# explorator_mainboard_v1_99mm.net
KiCad netlist of a schematic drawn in EAGLE
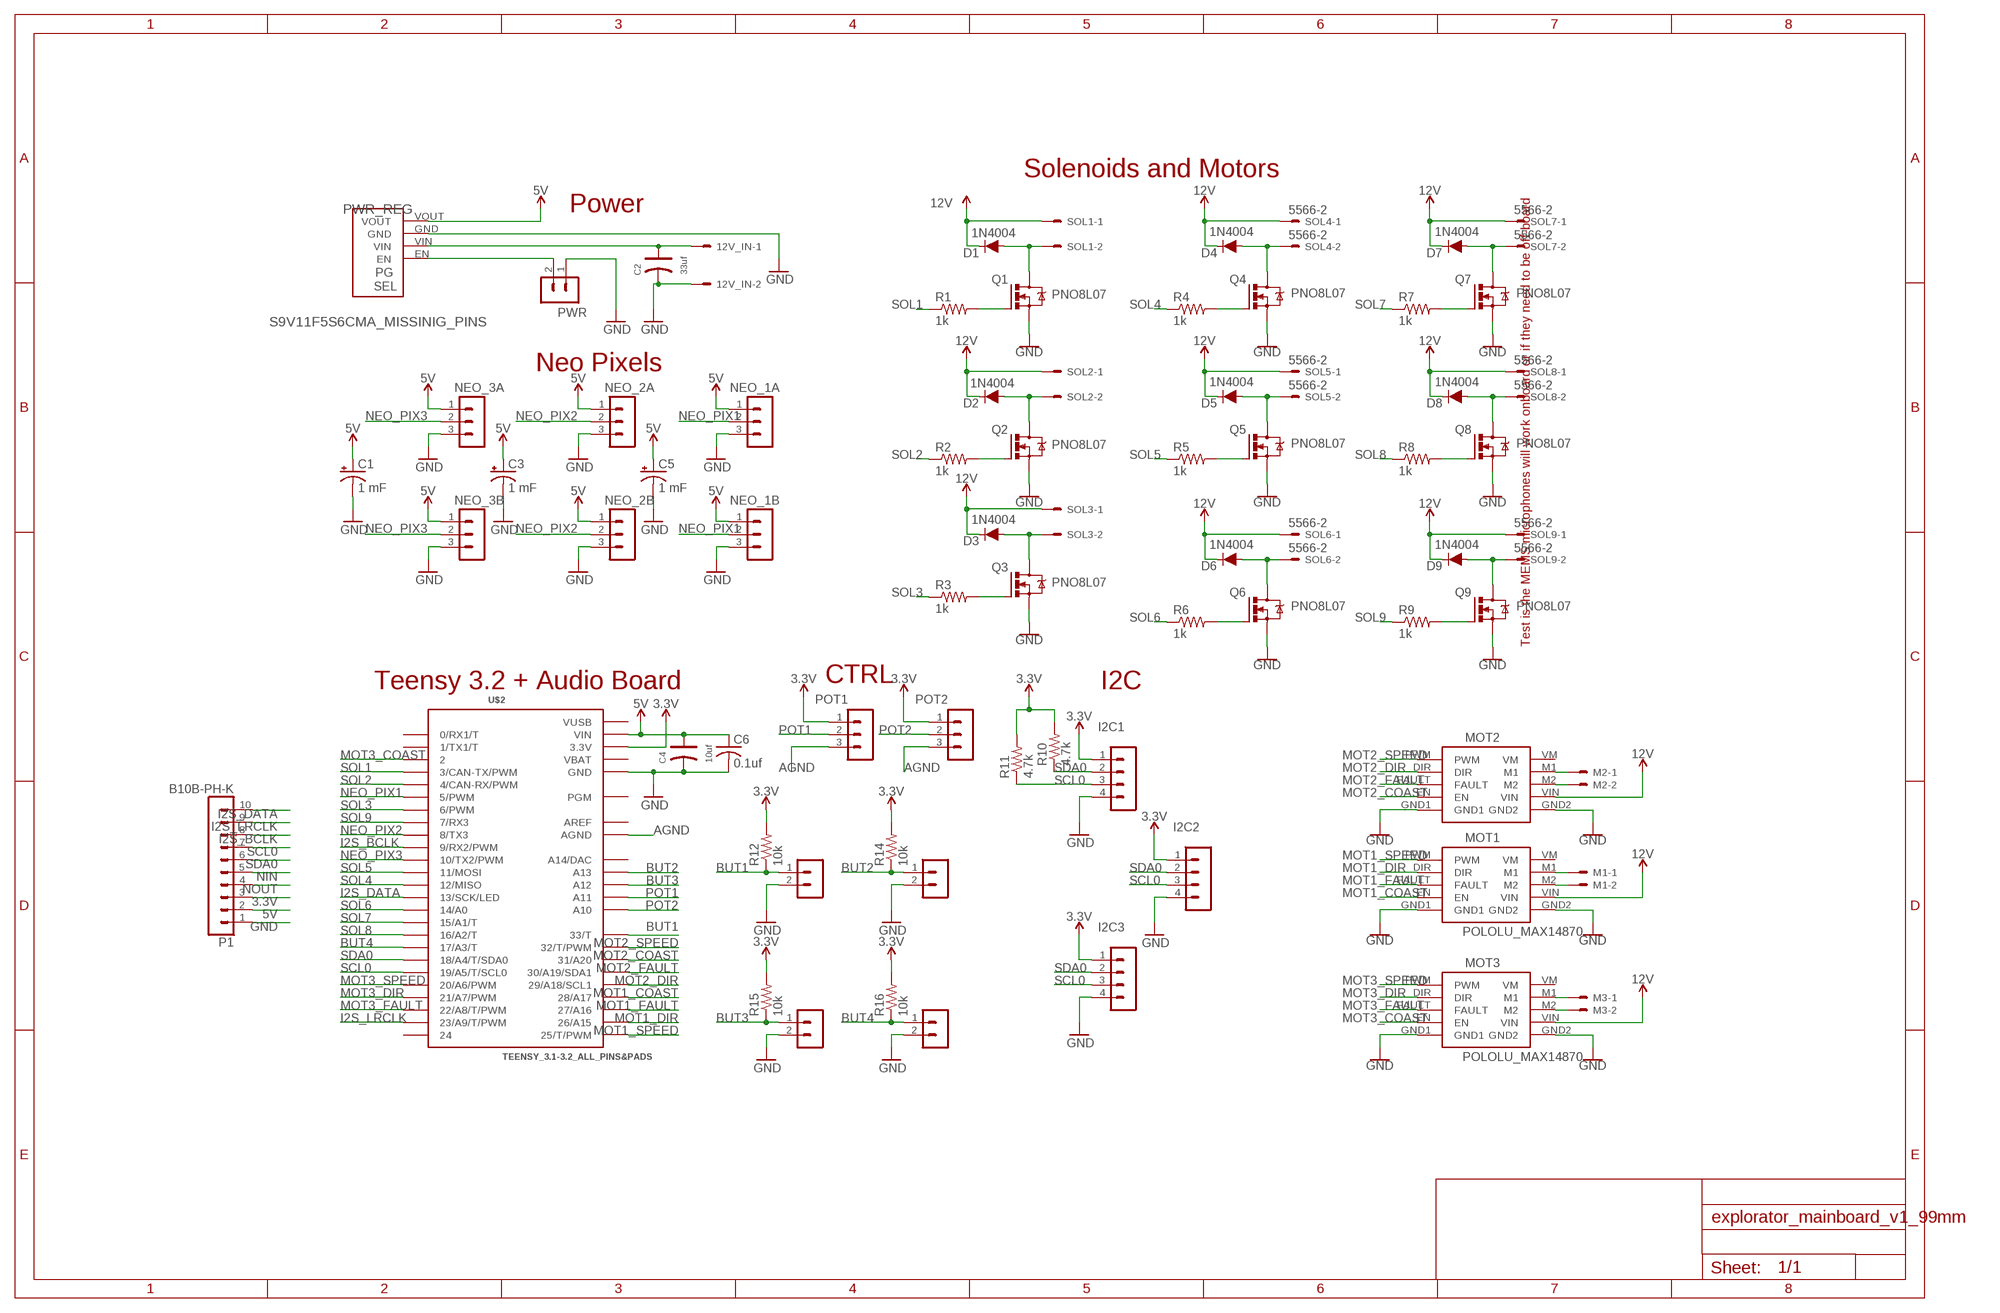
[diagram p0: schematic, sheet 1]

(export (version "E")
  (design (tool "Eeschema 10.0.6"))
  (components
    (comp (ref "12V_IN")
      (value "5566-2")
      (footprint "eagle-import:5566-2")
      (fields (field (name "MF") "MOLEX"))
      (libsource (lib "eagle-import") (part "5566-2"))
    )
    (comp (ref "BUT1")
      (value "B2B-PH-K")
      (footprint "eagle-import:B2B-PH-K")
      (libsource (lib "eagle-import") (part "B2B-PH-K"))
    )
    (comp (ref "BUT2")
      (value "B2B-PH-K")
      (footprint "eagle-import:B2B-PH-K")
      (libsource (lib "eagle-import") (part "B2B-PH-K"))
    )
    (comp (ref "BUT3")
      (value "B2B-PH-K")
      (footprint "eagle-import:B2B-PH-K")
      (libsource (lib "eagle-import") (part "B2B-PH-K"))
    )
    (comp (ref "BUT4")
      (value "B2B-PH-K")
      (footprint "eagle-import:B2B-PH-K")
      (libsource (lib "eagle-import") (part "B2B-PH-K"))
    )
    (comp (ref "C1")
      (value "1 mF")
      (footprint "eagle-import:UD-10X10_NICHICON")
      (libsource (lib "eagle-import") (part "CPOL-USUD-10X10"))
    )
    (comp (ref "C2")
      (value "33uf")
      (footprint "eagle-import:PC-D5.3MM")
      (fields (field (name "MPN") "KS 100uF/16V"))
      (libsource (lib "eagle-import") (part "DIP-ALUMINUM-47UF-16V(D5-H7MM)"))
    )
    (comp (ref "C3")
      (value "1 mF")
      (footprint "eagle-import:UD-10X10_NICHICON")
      (libsource (lib "eagle-import") (part "CPOL-USUD-10X10"))
    )
    (comp (ref "C4")
      (value "10uf")
      (footprint "eagle-import:PC-D5.3MM")
      (fields (field (name "MPN") "KS 100uF/16V"))
      (libsource (lib "eagle-import") (part "DIP-ALUMINUM-47UF-16V(D5-H7MM)"))
    )
    (comp (ref "C5")
      (value "1 mF")
      (footprint "eagle-import:UD-10X10_NICHICON")
      (libsource (lib "eagle-import") (part "CPOL-USUD-10X10"))
    )
    (comp (ref "C6")
      (value "0.1uf")
      (footprint "eagle-import:C2012")
      (libsource (lib "eagle-import") (part "C-USC2012"))
    )
    (comp (ref "D1")
      (value "1N4004")
      (footprint "eagle-import:DIOAD1138W86L465D235B")
      (libsource (lib "eagle-import") (part "1N4004"))
    )
    (comp (ref "D2")
      (value "1N4004")
      (footprint "eagle-import:DIOAD1138W86L465D235B")
      (libsource (lib "eagle-import") (part "1N4004"))
    )
    (comp (ref "D3")
      (value "1N4004")
      (footprint "eagle-import:DIOAD1138W86L465D235B")
      (libsource (lib "eagle-import") (part "1N4004"))
    )
    (comp (ref "D4")
      (value "1N4004")
      (footprint "eagle-import:DIOAD1138W86L465D235B")
      (libsource (lib "eagle-import") (part "1N4004"))
    )
    (comp (ref "D5")
      (value "1N4004")
      (footprint "eagle-import:DIOAD1138W86L465D235B")
      (libsource (lib "eagle-import") (part "1N4004"))
    )
    (comp (ref "D6")
      (value "1N4004")
      (footprint "eagle-import:DIOAD1138W86L465D235B")
      (libsource (lib "eagle-import") (part "1N4004"))
    )
    (comp (ref "D7")
      (value "1N4004")
      (footprint "eagle-import:DIOAD1138W86L465D235B")
      (libsource (lib "eagle-import") (part "1N4004"))
    )
    (comp (ref "D8")
      (value "1N4004")
      (footprint "eagle-import:DIOAD1138W86L465D235B")
      (libsource (lib "eagle-import") (part "1N4004"))
    )
    (comp (ref "D9")
      (value "1N4004")
      (footprint "eagle-import:DIOAD1138W86L465D235B")
      (libsource (lib "eagle-import") (part "1N4004"))
    )
    (comp (ref "I2C1")
      (value "B4B-PH-K")
      (footprint "eagle-import:B4B-PH-K")
      (libsource (lib "eagle-import") (part "B4B-PH-K"))
    )
    (comp (ref "I2C2")
      (value "B4B-PH-K")
      (footprint "eagle-import:B4B-PH-K")
      (libsource (lib "eagle-import") (part "B4B-PH-K"))
    )
    (comp (ref "I2C3")
      (value "B4B-PH-K")
      (footprint "eagle-import:B4B-PH-K")
      (libsource (lib "eagle-import") (part "B4B-PH-K"))
    )
    (comp (ref "M1")
      (value "5566-2")
      (footprint "eagle-import:5566-2")
      (fields (field (name "MF") "MOLEX"))
      (libsource (lib "eagle-import") (part "5566-2"))
    )
    (comp (ref "M2")
      (value "5566-2")
      (footprint "eagle-import:5566-2")
      (fields (field (name "MF") "MOLEX"))
      (libsource (lib "eagle-import") (part "5566-2"))
    )
    (comp (ref "M3")
      (value "5566-2")
      (footprint "eagle-import:5566-2")
      (fields (field (name "MF") "MOLEX"))
      (libsource (lib "eagle-import") (part "5566-2"))
    )
    (comp (ref "MOT1")
      (value "POLOLU_MAX14870")
      (footprint "eagle-import:POLOLU_MAX14870")
      (libsource (lib "eagle-import") (part "POLOLU_MAX14870"))
    )
    (comp (ref "MOT2")
      (value "POLOLU_MAX14870")
      (footprint "eagle-import:POLOLU_MAX14870")
      (libsource (lib "eagle-import") (part "POLOLU_MAX14870"))
    )
    (comp (ref "MOT3")
      (value "POLOLU_MAX14870")
      (footprint "eagle-import:POLOLU_MAX14870")
      (libsource (lib "eagle-import") (part "POLOLU_MAX14870"))
    )
    (comp (ref "NEO_1A")
      (value "B3B-PH-K")
      (footprint "eagle-import:B3B-PH-K")
      (libsource (lib "eagle-import") (part "B3B-PH-K"))
    )
    (comp (ref "NEO_1B")
      (value "B3B-PH-K")
      (footprint "eagle-import:B3B-PH-K")
      (libsource (lib "eagle-import") (part "B3B-PH-K"))
    )
    (comp (ref "NEO_2A")
      (value "B3B-PH-K")
      (footprint "eagle-import:B3B-PH-K")
      (libsource (lib "eagle-import") (part "B3B-PH-K"))
    )
    (comp (ref "NEO_2B")
      (value "B3B-PH-K")
      (footprint "eagle-import:B3B-PH-K")
      (libsource (lib "eagle-import") (part "B3B-PH-K"))
    )
    (comp (ref "NEO_3A")
      (value "B3B-PH-K")
      (footprint "eagle-import:B3B-PH-K")
      (libsource (lib "eagle-import") (part "B3B-PH-K"))
    )
    (comp (ref "NEO_3B")
      (value "B3B-PH-K")
      (footprint "eagle-import:B3B-PH-K")
      (libsource (lib "eagle-import") (part "B3B-PH-K"))
    )
    (comp (ref "P1")
      (value "B10B-PH-K")
      (footprint "eagle-import:B10B-PH-K")
      (libsource (lib "eagle-import") (part "B10B-PH-K"))
    )
    (comp (ref "POT1")
      (value "B3B-PH-K")
      (footprint "eagle-import:B3B-PH-K")
      (libsource (lib "eagle-import") (part "B3B-PH-K"))
    )
    (comp (ref "POT2")
      (value "B3B-PH-K")
      (footprint "eagle-import:B3B-PH-K")
      (libsource (lib "eagle-import") (part "B3B-PH-K"))
    )
    (comp (ref "PWR")
      (value "B2B-PH-K")
      (footprint "eagle-import:B2B-PH-K")
      (libsource (lib "eagle-import") (part "B2B-PH-K"))
    )
    (comp (ref "PWR_REG")
      (value "S9V11F5S6CMA_MISSINIG_PINS")
      (footprint "eagle-import:S9V11F3S5CMA_MISSING_PINS")
      (libsource (lib "eagle-import") (part "S9V11F5S6CMA_MISSINIG_PINS"))
    )
    (comp (ref "Q1")
      (value "PNO8L07")
      (footprint "eagle-import:TO220BV")
      (libsource (lib "eagle-import") (part "IRF540"))
    )
    (comp (ref "Q2")
      (value "PNO8L07")
      (footprint "eagle-import:TO220BV")
      (libsource (lib "eagle-import") (part "IRF540"))
    )
    (comp (ref "Q3")
      (value "PNO8L07")
      (footprint "eagle-import:TO220BV")
      (libsource (lib "eagle-import") (part "IRF540"))
    )
    (comp (ref "Q4")
      (value "PNO8L07")
      (footprint "eagle-import:TO220BV")
      (libsource (lib "eagle-import") (part "IRF540"))
    )
    (comp (ref "Q5")
      (value "PNO8L07")
      (footprint "eagle-import:TO220BV")
      (libsource (lib "eagle-import") (part "IRF540"))
    )
    (comp (ref "Q6")
      (value "PNO8L07")
      (footprint "eagle-import:TO220BV")
      (libsource (lib "eagle-import") (part "IRF540"))
    )
    (comp (ref "Q7")
      (value "PNO8L07")
      (footprint "eagle-import:TO220BV")
      (libsource (lib "eagle-import") (part "IRF540"))
    )
    (comp (ref "Q8")
      (value "PNO8L07")
      (footprint "eagle-import:TO220BV")
      (libsource (lib "eagle-import") (part "IRF540"))
    )
    (comp (ref "Q9")
      (value "PNO8L07")
      (footprint "eagle-import:TO220BV")
      (libsource (lib "eagle-import") (part "IRF540"))
    )
    (comp (ref "R1")
      (value "1k")
      (footprint "eagle-import:R0805")
      (libsource (lib "eagle-import") (part "R-US_R0805"))
    )
    (comp (ref "R2")
      (value "1k")
      (footprint "eagle-import:R0805")
      (libsource (lib "eagle-import") (part "R-US_R0805"))
    )
    (comp (ref "R3")
      (value "1k")
      (footprint "eagle-import:R0805")
      (libsource (lib "eagle-import") (part "R-US_R0805"))
    )
    (comp (ref "R4")
      (value "1k")
      (footprint "eagle-import:R0805")
      (libsource (lib "eagle-import") (part "R-US_R0805"))
    )
    (comp (ref "R5")
      (value "1k")
      (footprint "eagle-import:R0805")
      (libsource (lib "eagle-import") (part "R-US_R0805"))
    )
    (comp (ref "R6")
      (value "1k")
      (footprint "eagle-import:R0805")
      (libsource (lib "eagle-import") (part "R-US_R0805"))
    )
    (comp (ref "R7")
      (value "1k")
      (footprint "eagle-import:R0805")
      (libsource (lib "eagle-import") (part "R-US_R0805"))
    )
    (comp (ref "R8")
      (value "1k")
      (footprint "eagle-import:R0805")
      (libsource (lib "eagle-import") (part "R-US_R0805"))
    )
    (comp (ref "R9")
      (value "1k")
      (footprint "eagle-import:R0805")
      (libsource (lib "eagle-import") (part "R-US_R0805"))
    )
    (comp (ref "R10")
      (value "4.7k")
      (footprint "eagle-import:R0805")
      (libsource (lib "eagle-import") (part "R-US_R0805"))
    )
    (comp (ref "R11")
      (value "4.7k")
      (footprint "eagle-import:R0805")
      (libsource (lib "eagle-import") (part "R-US_R0805"))
    )
    (comp (ref "R12")
      (value "10k")
      (footprint "eagle-import:R0805")
      (libsource (lib "eagle-import") (part "R-US_R0805"))
    )
    (comp (ref "R14")
      (value "10k")
      (footprint "eagle-import:R0805")
      (libsource (lib "eagle-import") (part "R-US_R0805"))
    )
    (comp (ref "R15")
      (value "10k")
      (footprint "eagle-import:R0805")
      (libsource (lib "eagle-import") (part "R-US_R0805"))
    )
    (comp (ref "R16")
      (value "10k")
      (footprint "eagle-import:R0805")
      (libsource (lib "eagle-import") (part "R-US_R0805"))
    )
    (comp (ref "SOL1")
      (value "5566-2")
      (footprint "eagle-import:5566-2")
      (fields (field (name "MF") "MOLEX"))
      (libsource (lib "eagle-import") (part "5566-2"))
    )
    (comp (ref "SOL2")
      (value "5566-2")
      (footprint "eagle-import:5566-2")
      (fields (field (name "MF") "MOLEX"))
      (libsource (lib "eagle-import") (part "5566-2"))
    )
    (comp (ref "SOL3")
      (value "5566-2")
      (footprint "eagle-import:5566-2")
      (fields (field (name "MF") "MOLEX"))
      (libsource (lib "eagle-import") (part "5566-2"))
    )
    (comp (ref "SOL4")
      (value "5566-2")
      (footprint "eagle-import:5566-2")
      (fields (field (name "MF") "MOLEX"))
      (libsource (lib "eagle-import") (part "5566-2"))
    )
    (comp (ref "SOL5")
      (value "5566-2")
      (footprint "eagle-import:5566-2")
      (fields (field (name "MF") "MOLEX"))
      (libsource (lib "eagle-import") (part "5566-2"))
    )
    (comp (ref "SOL6")
      (value "5566-2")
      (footprint "eagle-import:5566-2")
      (fields (field (name "MF") "MOLEX"))
      (libsource (lib "eagle-import") (part "5566-2"))
    )
    (comp (ref "SOL7")
      (value "5566-2")
      (footprint "eagle-import:5566-2")
      (fields (field (name "MF") "MOLEX"))
      (libsource (lib "eagle-import") (part "5566-2"))
    )
    (comp (ref "SOL8")
      (value "5566-2")
      (footprint "eagle-import:5566-2")
      (fields (field (name "MF") "MOLEX"))
      (libsource (lib "eagle-import") (part "5566-2"))
    )
    (comp (ref "SOL9")
      (value "5566-2")
      (footprint "eagle-import:5566-2")
      (fields (field (name "MF") "MOLEX"))
      (libsource (lib "eagle-import") (part "5566-2"))
    )
    (comp (ref "U$2")
      (value "TEENSY_3.1-3.2_ALL_PINS&PADS")
      (footprint "eagle-import:TEENSY_3.0-3.2_ALL_PINS_&_PADS")
      (libsource (lib "eagle-import") (part "TEENSY_3.1-3.2_ALL_PINS&PADS"))
    )
  )
  (nets
    (net (code "1") (name "/AGND") (class "Default")
      (node (ref "POT1") (pin "3") (pinfunction "3_3") (pintype "passive"))
      (node (ref "POT2") (pin "3") (pinfunction "3_3") (pintype "passive"))
      (node (ref "U$2") (pin "AGND") (pinfunction "AGND_AGND") (pintype "power_in"))
    )
    (net (code "2") (name "/AREF") (class "Default")
      (node (ref "U$2") (pin "AREF") (pinfunction "AREF_AREF") (pintype "power_in"))
    )
    (net (code "3") (name "/BUT1") (class "Default")
      (node (ref "BUT1") (pin "1") (pinfunction "1_1") (pintype "passive"))
      (node (ref "R12") (pin "1") (pinfunction "1_1") (pintype "passive"))
      (node (ref "U$2") (pin "33") (pinfunction "33/T_33") (pintype "bidirectional"))
    )
    (net (code "4") (name "/BUT2") (class "Default")
      (node (ref "BUT2") (pin "1") (pinfunction "1_1") (pintype "passive"))
      (node (ref "R14") (pin "1") (pinfunction "1_1") (pintype "passive"))
      (node (ref "U$2") (pin "A13") (pinfunction "A13_A13") (pintype "bidirectional"))
    )
    (net (code "5") (name "/BUT3") (class "Default")
      (node (ref "BUT3") (pin "1") (pinfunction "1_1") (pintype "passive"))
      (node (ref "R15") (pin "1") (pinfunction "1_1") (pintype "passive"))
      (node (ref "U$2") (pin "A12") (pinfunction "A12_A12") (pintype "bidirectional"))
    )
    (net (code "6") (name "/BUT4") (class "Default")
      (node (ref "BUT4") (pin "1") (pinfunction "1_1") (pintype "passive"))
      (node (ref "R16") (pin "1") (pinfunction "1_1") (pintype "passive"))
      (node (ref "U$2") (pin "17/A3") (pinfunction "17/A3/T_17/A3") (pintype "bidirectional"))
    )
    (net (code "7") (name "/I2S_BCLK") (class "Default")
      (node (ref "P1") (pin "8") (pinfunction "8_8") (pintype "passive"))
      (node (ref "U$2") (pin "9") (pinfunction "9/RX2/PWM_9") (pintype "bidirectional"))
    )
    (net (code "8") (name "/I2S_DATA") (class "Default")
      (node (ref "P1") (pin "10") (pinfunction "10_10") (pintype "passive"))
      (node (ref "U$2") (pin "13") (pinfunction "13/SCK/LED_13") (pintype "bidirectional"))
    )
    (net (code "9") (name "/I2S_LRCLK") (class "Default")
      (node (ref "P1") (pin "9") (pinfunction "9_9") (pintype "passive"))
      (node (ref "U$2") (pin "23/A9") (pinfunction "23/A9/T/PWM_23/A9") (pintype "bidirectional"))
    )
    (net (code "10") (name "/MOT1_COAST") (class "Default")
      (node (ref "MOT1") (pin "EN") (pinfunction "EN_EN") (pintype "bidirectional"))
      (node (ref "U$2") (pin "28") (pinfunction "28/A17_28") (pintype "bidirectional"))
    )
    (net (code "11") (name "/MOT1_DIR") (class "Default")
      (node (ref "MOT1") (pin "DIR") (pinfunction "DIR_DIR") (pintype "bidirectional"))
      (node (ref "U$2") (pin "26") (pinfunction "26/A15_26") (pintype "bidirectional"))
    )
    (net (code "12") (name "/MOT1_FAULT") (class "Default")
      (node (ref "MOT1") (pin "FAULT") (pinfunction "FAULT_FAULT") (pintype "bidirectional"))
      (node (ref "U$2") (pin "27") (pinfunction "27/A16_27") (pintype "bidirectional"))
    )
    (net (code "13") (name "/MOT1_SPEED") (class "Default")
      (node (ref "MOT1") (pin "PWM") (pinfunction "PWM_PWM") (pintype "bidirectional"))
      (node (ref "U$2") (pin "25") (pinfunction "25/T/PWM_25") (pintype "bidirectional"))
    )
    (net (code "14") (name "/MOT2_COAST") (class "Default")
      (node (ref "MOT2") (pin "EN") (pinfunction "EN_EN") (pintype "bidirectional"))
      (node (ref "U$2") (pin "31") (pinfunction "31/A20_31") (pintype "bidirectional"))
    )
    (net (code "15") (name "/MOT2_DIR") (class "Default")
      (node (ref "MOT2") (pin "DIR") (pinfunction "DIR_DIR") (pintype "bidirectional"))
      (node (ref "U$2") (pin "29") (pinfunction "29/A18/SCL1_29") (pintype "bidirectional"))
    )
    (net (code "16") (name "/MOT2_FAULT") (class "Default")
      (node (ref "MOT2") (pin "FAULT") (pinfunction "FAULT_FAULT") (pintype "bidirectional"))
      (node (ref "U$2") (pin "30") (pinfunction "30/A19/SDA1_30") (pintype "bidirectional"))
    )
    (net (code "17") (name "/MOT2_SPEED") (class "Default")
      (node (ref "MOT2") (pin "PWM") (pinfunction "PWM_PWM") (pintype "bidirectional"))
      (node (ref "U$2") (pin "32") (pinfunction "32/T/PWM_32") (pintype "bidirectional"))
    )
    (net (code "18") (name "/MOT3_COAST") (class "Default")
      (node (ref "MOT3") (pin "EN") (pinfunction "EN_EN") (pintype "bidirectional"))
      (node (ref "U$2") (pin "2") (pinfunction "2_2") (pintype "bidirectional"))
    )
    (net (code "19") (name "/MOT3_DIR") (class "Default")
      (node (ref "MOT3") (pin "DIR") (pinfunction "DIR_DIR") (pintype "bidirectional"))
      (node (ref "U$2") (pin "21/A7") (pinfunction "21/A7/PWM_21/A7") (pintype "bidirectional"))
    )
    (net (code "20") (name "/MOT3_FAULT") (class "Default")
      (node (ref "MOT3") (pin "FAULT") (pinfunction "FAULT_FAULT") (pintype "bidirectional"))
      (node (ref "U$2") (pin "22/A8") (pinfunction "22/A8/T/PWM_22/A8") (pintype "bidirectional"))
    )
    (net (code "21") (name "/MOT3_SPEED") (class "Default")
      (node (ref "MOT3") (pin "PWM") (pinfunction "PWM_PWM") (pintype "bidirectional"))
      (node (ref "U$2") (pin "20/A6") (pinfunction "20/A6/PWM_20/A6") (pintype "bidirectional"))
    )
    (net (code "22") (name "/NEO_PIX1") (class "Default")
      (node (ref "NEO_1A") (pin "2") (pinfunction "2_2") (pintype "passive"))
      (node (ref "NEO_1B") (pin "2") (pinfunction "2_2") (pintype "passive"))
      (node (ref "U$2") (pin "5") (pinfunction "5/PWM_5") (pintype "bidirectional"))
    )
    (net (code "23") (name "/NEO_PIX2") (class "Default")
      (node (ref "NEO_2A") (pin "2") (pinfunction "2_2") (pintype "passive"))
      (node (ref "NEO_2B") (pin "2") (pinfunction "2_2") (pintype "passive"))
      (node (ref "U$2") (pin "8") (pinfunction "8/TX3_8") (pintype "bidirectional"))
    )
    (net (code "24") (name "/NEO_PIX3") (class "Default")
      (node (ref "NEO_3A") (pin "2") (pinfunction "2_2") (pintype "passive"))
      (node (ref "NEO_3B") (pin "2") (pinfunction "2_2") (pintype "passive"))
      (node (ref "U$2") (pin "10") (pinfunction "10/TX2/PWM_10") (pintype "bidirectional"))
    )
    (net (code "25") (name "/NIN") (class "Default")
      (node (ref "P1") (pin "5") (pinfunction "5_5") (pintype "passive"))
    )
    (net (code "26") (name "/NOUT") (class "Default")
      (node (ref "P1") (pin "4") (pinfunction "4_4") (pintype "passive"))
    )
    (net (code "27") (name "/POT1") (class "Default")
      (node (ref "POT1") (pin "2") (pinfunction "2_2") (pintype "passive"))
      (node (ref "U$2") (pin "A11") (pinfunction "A11_A11") (pintype "bidirectional"))
    )
    (net (code "28") (name "/POT2") (class "Default")
      (node (ref "POT2") (pin "2") (pinfunction "2_2") (pintype "passive"))
      (node (ref "U$2") (pin "A10") (pinfunction "A10_A10") (pintype "bidirectional"))
    )
    (net (code "29") (name "/SCL0") (class "Default")
      (node (ref "I2C1") (pin "3") (pinfunction "3_3") (pintype "passive"))
      (node (ref "I2C2") (pin "3") (pinfunction "3_3") (pintype "passive"))
      (node (ref "I2C3") (pin "3") (pinfunction "3_3") (pintype "passive"))
      (node (ref "P1") (pin "7") (pinfunction "7_7") (pintype "passive"))
      (node (ref "R11") (pin "1") (pinfunction "1_1") (pintype "passive"))
      (node (ref "U$2") (pin "19/A5") (pinfunction "19/A5/T/SCL0_19/A5") (pintype "bidirectional"))
    )
    (net (code "30") (name "/SDA0") (class "Default")
      (node (ref "I2C1") (pin "2") (pinfunction "2_2") (pintype "passive"))
      (node (ref "I2C2") (pin "2") (pinfunction "2_2") (pintype "passive"))
      (node (ref "I2C3") (pin "2") (pinfunction "2_2") (pintype "passive"))
      (node (ref "P1") (pin "6") (pinfunction "6_6") (pintype "passive"))
      (node (ref "R10") (pin "1") (pinfunction "1_1") (pintype "passive"))
      (node (ref "U$2") (pin "18/A4") (pinfunction "18/A4/T/SDA0_18/A4") (pintype "bidirectional"))
    )
    (net (code "31") (name "/SOL1") (class "Default")
      (node (ref "R1") (pin "1") (pinfunction "1_1") (pintype "passive"))
      (node (ref "U$2") (pin "3") (pinfunction "3/CAN-TX/PWM_3") (pintype "bidirectional"))
    )
    (net (code "32") (name "/SOL2") (class "Default")
      (node (ref "R2") (pin "1") (pinfunction "1_1") (pintype "passive"))
      (node (ref "U$2") (pin "4") (pinfunction "4/CAN-RX/PWM_4") (pintype "bidirectional"))
    )
    (net (code "33") (name "/SOL3") (class "Default")
      (node (ref "R3") (pin "1") (pinfunction "1_1") (pintype "passive"))
      (node (ref "U$2") (pin "6") (pinfunction "6/PWM_6") (pintype "bidirectional"))
    )
    (net (code "34") (name "/SOL4") (class "Default")
      (node (ref "R4") (pin "1") (pinfunction "1_1") (pintype "passive"))
      (node (ref "U$2") (pin "12") (pinfunction "12/MISO_12") (pintype "bidirectional"))
    )
    (net (code "35") (name "/SOL5") (class "Default")
      (node (ref "R5") (pin "1") (pinfunction "1_1") (pintype "passive"))
      (node (ref "U$2") (pin "11") (pinfunction "11/MOSI_11") (pintype "bidirectional"))
    )
    (net (code "36") (name "/SOL6") (class "Default")
      (node (ref "R6") (pin "1") (pinfunction "1_1") (pintype "passive"))
      (node (ref "U$2") (pin "14/A0") (pinfunction "14/A0_14/A0") (pintype "bidirectional"))
    )
    (net (code "37") (name "/SOL7") (class "Default")
      (node (ref "R7") (pin "1") (pinfunction "1_1") (pintype "passive"))
      (node (ref "U$2") (pin "15/A1") (pinfunction "15/A1/T_15/A1") (pintype "bidirectional"))
    )
    (net (code "38") (name "/SOL8") (class "Default")
      (node (ref "R8") (pin "1") (pinfunction "1_1") (pintype "passive"))
      (node (ref "U$2") (pin "16/A2") (pinfunction "16/A2/T_16/A2") (pintype "bidirectional"))
    )
    (net (code "39") (name "/SOL9") (class "Default")
      (node (ref "R9") (pin "1") (pinfunction "1_1") (pintype "passive"))
      (node (ref "U$2") (pin "7") (pinfunction "7/RX3_7") (pintype "bidirectional"))
    )
    (net (code "40") (name "/VBAT") (class "Default")
      (node (ref "U$2") (pin "VBAT") (pinfunction "VBAT_VBAT") (pintype "power_in"))
    )
    (net (code "41") (name "/VUSB") (class "Default")
      (node (ref "U$2") (pin "VUSB") (pinfunction "VUSB_VUSB") (pintype "power_in"))
    )
    (net (code "42") (name "3.3V") (class "Default")
      (node (ref "I2C1") (pin "1") (pinfunction "1_1") (pintype "passive"))
      (node (ref "I2C2") (pin "1") (pinfunction "1_1") (pintype "passive"))
      (node (ref "I2C3") (pin "1") (pinfunction "1_1") (pintype "passive"))
      (node (ref "P1") (pin "3") (pinfunction "3_3") (pintype "passive"))
      (node (ref "POT1") (pin "1") (pinfunction "1_1") (pintype "passive"))
      (node (ref "POT2") (pin "1") (pinfunction "1_1") (pintype "passive"))
      (node (ref "R10") (pin "2") (pinfunction "2_2") (pintype "passive"))
      (node (ref "R11") (pin "2") (pinfunction "2_2") (pintype "passive"))
      (node (ref "R12") (pin "2") (pinfunction "2_2") (pintype "passive"))
      (node (ref "R14") (pin "2") (pinfunction "2_2") (pintype "passive"))
      (node (ref "R15") (pin "2") (pinfunction "2_2") (pintype "passive"))
      (node (ref "R16") (pin "2") (pinfunction "2_2") (pintype "passive"))
      (node (ref "U$2") (pin "3.3V") (pinfunction "3.3V_3.3V") (pintype "power_in"))
      (node (ref "U$2") (pin "3.3V1") (pinfunction "3.3V_3.3V1") (pintype "power_in"))
      (node (ref "U$2") (pin "3.3V2") (pinfunction "3.3V_3.3V2") (pintype "power_in"))
    )
    (net (code "43") (name "5V") (class "Default")
      (node (ref "C1") (pin "+") (pinfunction "+_+") (pintype "passive"))
      (node (ref "C3") (pin "+") (pinfunction "+_+") (pintype "passive"))
      (node (ref "C4") (pin "+") (pinfunction "+_+") (pintype "passive"))
      (node (ref "C5") (pin "+") (pinfunction "+_+") (pintype "passive"))
      (node (ref "C6") (pin "1") (pinfunction "1_1") (pintype "passive"))
      (node (ref "NEO_1A") (pin "1") (pinfunction "1_1") (pintype "passive"))
      (node (ref "NEO_1B") (pin "1") (pinfunction "1_1") (pintype "passive"))
      (node (ref "NEO_2A") (pin "1") (pinfunction "1_1") (pintype "passive"))
      (node (ref "NEO_2B") (pin "1") (pinfunction "1_1") (pintype "passive"))
      (node (ref "NEO_3A") (pin "1") (pinfunction "1_1") (pintype "passive"))
      (node (ref "NEO_3B") (pin "1") (pinfunction "1_1") (pintype "passive"))
      (node (ref "P1") (pin "2") (pinfunction "2_2") (pintype "passive"))
      (node (ref "PWR_REG") (pin "VOUT") (pinfunction "VOUT_VOUT") (pintype "bidirectional"))
      (node (ref "U$2") (pin "VIN") (pinfunction "VIN_VIN") (pintype "power_in"))
    )
    (net (code "44") (name "12V") (class "Default")
      (node (ref "12V_IN") (pin "1") (pinfunction "S_1") (pintype "passive"))
      (node (ref "C2") (pin "+") (pinfunction "+_+") (pintype "passive"))
      (node (ref "D1") (pin "2") (pinfunction "C_2") (pintype "passive"))
      (node (ref "D2") (pin "2") (pinfunction "C_2") (pintype "passive"))
      (node (ref "D3") (pin "2") (pinfunction "C_2") (pintype "passive"))
      (node (ref "D4") (pin "2") (pinfunction "C_2") (pintype "passive"))
      (node (ref "D5") (pin "2") (pinfunction "C_2") (pintype "passive"))
      (node (ref "D6") (pin "2") (pinfunction "C_2") (pintype "passive"))
      (node (ref "D7") (pin "2") (pinfunction "C_2") (pintype "passive"))
      (node (ref "D8") (pin "2") (pinfunction "C_2") (pintype "passive"))
      (node (ref "D9") (pin "2") (pinfunction "C_2") (pintype "passive"))
      (node (ref "MOT1") (pin "VIN") (pinfunction "VIN_VIN") (pintype "bidirectional"))
      (node (ref "MOT2") (pin "VIN") (pinfunction "VIN_VIN") (pintype "bidirectional"))
      (node (ref "MOT3") (pin "VIN") (pinfunction "VIN_VIN") (pintype "bidirectional"))
      (node (ref "PWR_REG") (pin "VIN") (pinfunction "VIN_VIN") (pintype "bidirectional"))
      (node (ref "SOL1") (pin "1") (pinfunction "S_1") (pintype "passive"))
      (node (ref "SOL2") (pin "1") (pinfunction "S_1") (pintype "passive"))
      (node (ref "SOL3") (pin "1") (pinfunction "S_1") (pintype "passive"))
      (node (ref "SOL4") (pin "1") (pinfunction "S_1") (pintype "passive"))
      (node (ref "SOL5") (pin "1") (pinfunction "S_1") (pintype "passive"))
      (node (ref "SOL6") (pin "1") (pinfunction "S_1") (pintype "passive"))
      (node (ref "SOL7") (pin "1") (pinfunction "S_1") (pintype "passive"))
      (node (ref "SOL8") (pin "1") (pinfunction "S_1") (pintype "passive"))
      (node (ref "SOL9") (pin "1") (pinfunction "S_1") (pintype "passive"))
    )
    (net (code "45") (name "GND") (class "Default")
      (node (ref "12V_IN") (pin "2") (pinfunction "S_2") (pintype "passive"))
      (node (ref "BUT1") (pin "2") (pinfunction "2_2") (pintype "passive"))
      (node (ref "BUT2") (pin "2") (pinfunction "2_2") (pintype "passive"))
      (node (ref "BUT3") (pin "2") (pinfunction "2_2") (pintype "passive"))
      (node (ref "BUT4") (pin "2") (pinfunction "2_2") (pintype "passive"))
      (node (ref "C1") (pin "-") (pinfunction "-_-") (pintype "passive"))
      (node (ref "C2") (pin "-") (pinfunction "-_-") (pintype "passive"))
      (node (ref "C3") (pin "-") (pinfunction "-_-") (pintype "passive"))
      (node (ref "C4") (pin "-") (pinfunction "-_-") (pintype "passive"))
      (node (ref "C5") (pin "-") (pinfunction "-_-") (pintype "passive"))
      (node (ref "C6") (pin "2") (pinfunction "2_2") (pintype "passive"))
      (node (ref "I2C1") (pin "4") (pinfunction "4_4") (pintype "passive"))
      (node (ref "I2C2") (pin "4") (pinfunction "4_4") (pintype "passive"))
      (node (ref "I2C3") (pin "4") (pinfunction "4_4") (pintype "passive"))
      (node (ref "MOT1") (pin "GND1") (pinfunction "GND1_GND1") (pintype "bidirectional"))
      (node (ref "MOT1") (pin "GND2") (pinfunction "GND2_GND2") (pintype "bidirectional"))
      (node (ref "MOT2") (pin "GND1") (pinfunction "GND1_GND1") (pintype "bidirectional"))
      (node (ref "MOT2") (pin "GND2") (pinfunction "GND2_GND2") (pintype "bidirectional"))
      (node (ref "MOT3") (pin "GND1") (pinfunction "GND1_GND1") (pintype "bidirectional"))
      (node (ref "MOT3") (pin "GND2") (pinfunction "GND2_GND2") (pintype "bidirectional"))
      (node (ref "NEO_1A") (pin "3") (pinfunction "3_3") (pintype "passive"))
      (node (ref "NEO_1B") (pin "3") (pinfunction "3_3") (pintype "passive"))
      (node (ref "NEO_2A") (pin "3") (pinfunction "3_3") (pintype "passive"))
      (node (ref "NEO_2B") (pin "3") (pinfunction "3_3") (pintype "passive"))
      (node (ref "NEO_3A") (pin "3") (pinfunction "3_3") (pintype "passive"))
      (node (ref "NEO_3B") (pin "3") (pinfunction "3_3") (pintype "passive"))
      (node (ref "P1") (pin "1") (pinfunction "1_1") (pintype "passive"))
      (node (ref "PWR") (pin "1") (pinfunction "1_1") (pintype "passive"))
      (node (ref "PWR_REG") (pin "GND") (pinfunction "GND_GND") (pintype "bidirectional"))
      (node (ref "Q1") (pin "S") (pinfunction "S_S") (pintype "passive"))
      (node (ref "Q2") (pin "S") (pinfunction "S_S") (pintype "passive"))
      (node (ref "Q3") (pin "S") (pinfunction "S_S") (pintype "passive"))
      (node (ref "Q4") (pin "S") (pinfunction "S_S") (pintype "passive"))
      (node (ref "Q5") (pin "S") (pinfunction "S_S") (pintype "passive"))
      (node (ref "Q6") (pin "S") (pinfunction "S_S") (pintype "passive"))
      (node (ref "Q7") (pin "S") (pinfunction "S_S") (pintype "passive"))
      (node (ref "Q8") (pin "S") (pinfunction "S_S") (pintype "passive"))
      (node (ref "Q9") (pin "S") (pinfunction "S_S") (pintype "passive"))
      (node (ref "U$2") (pin "GND") (pinfunction "GND_GND") (pintype "power_in"))
      (node (ref "U$2") (pin "GND1") (pinfunction "GND_GND1") (pintype "power_in"))
      (node (ref "U$2") (pin "GND2") (pinfunction "GND_GND2") (pintype "power_in"))
    )
    (net (code "46") (name "Net-(D1-A)") (class "Default")
      (node (ref "D1") (pin "1") (pinfunction "A_1") (pintype "passive"))
      (node (ref "Q1") (pin "D") (pinfunction "D_D") (pintype "passive"))
      (node (ref "SOL1") (pin "2") (pinfunction "S_2") (pintype "passive"))
    )
    (net (code "47") (name "Net-(D2-A)") (class "Default")
      (node (ref "D2") (pin "1") (pinfunction "A_1") (pintype "passive"))
      (node (ref "Q2") (pin "D") (pinfunction "D_D") (pintype "passive"))
      (node (ref "SOL2") (pin "2") (pinfunction "S_2") (pintype "passive"))
    )
    (net (code "48") (name "Net-(D3-A)") (class "Default")
      (node (ref "D3") (pin "1") (pinfunction "A_1") (pintype "passive"))
      (node (ref "Q3") (pin "D") (pinfunction "D_D") (pintype "passive"))
      (node (ref "SOL3") (pin "2") (pinfunction "S_2") (pintype "passive"))
    )
    (net (code "49") (name "Net-(D4-A)") (class "Default")
      (node (ref "D4") (pin "1") (pinfunction "A_1") (pintype "passive"))
      (node (ref "Q4") (pin "D") (pinfunction "D_D") (pintype "passive"))
      (node (ref "SOL4") (pin "2") (pinfunction "S_2") (pintype "passive"))
    )
    (net (code "50") (name "Net-(D5-A)") (class "Default")
      (node (ref "D5") (pin "1") (pinfunction "A_1") (pintype "passive"))
      (node (ref "Q5") (pin "D") (pinfunction "D_D") (pintype "passive"))
      (node (ref "SOL5") (pin "2") (pinfunction "S_2") (pintype "passive"))
    )
    (net (code "51") (name "Net-(D6-A)") (class "Default")
      (node (ref "D6") (pin "1") (pinfunction "A_1") (pintype "passive"))
      (node (ref "Q6") (pin "D") (pinfunction "D_D") (pintype "passive"))
      (node (ref "SOL6") (pin "2") (pinfunction "S_2") (pintype "passive"))
    )
    (net (code "52") (name "Net-(D7-A)") (class "Default")
      (node (ref "D7") (pin "1") (pinfunction "A_1") (pintype "passive"))
      (node (ref "Q7") (pin "D") (pinfunction "D_D") (pintype "passive"))
      (node (ref "SOL7") (pin "2") (pinfunction "S_2") (pintype "passive"))
    )
    (net (code "53") (name "Net-(D8-A)") (class "Default")
      (node (ref "D8") (pin "1") (pinfunction "A_1") (pintype "passive"))
      (node (ref "Q8") (pin "D") (pinfunction "D_D") (pintype "passive"))
      (node (ref "SOL8") (pin "2") (pinfunction "S_2") (pintype "passive"))
    )
    (net (code "54") (name "Net-(D9-A)") (class "Default")
      (node (ref "D9") (pin "1") (pinfunction "A_1") (pintype "passive"))
      (node (ref "Q9") (pin "D") (pinfunction "D_D") (pintype "passive"))
      (node (ref "SOL9") (pin "2") (pinfunction "S_2") (pintype "passive"))
    )
    (net (code "55") (name "Net-(M1A-S)") (class "Default")
      (node (ref "M1") (pin "1") (pinfunction "S_1") (pintype "passive"))
      (node (ref "MOT1") (pin "M1") (pinfunction "M1_M1") (pintype "bidirectional"))
    )
    (net (code "56") (name "Net-(M1B-S)") (class "Default")
      (node (ref "M1") (pin "2") (pinfunction "S_2") (pintype "passive"))
      (node (ref "MOT1") (pin "M2") (pinfunction "M2_M2") (pintype "bidirectional"))
    )
    (net (code "57") (name "Net-(M2A-S)") (class "Default")
      (node (ref "M2") (pin "1") (pinfunction "S_1") (pintype "passive"))
      (node (ref "MOT2") (pin "M1") (pinfunction "M1_M1") (pintype "bidirectional"))
    )
    (net (code "58") (name "Net-(M2B-S)") (class "Default")
      (node (ref "M2") (pin "2") (pinfunction "S_2") (pintype "passive"))
      (node (ref "MOT2") (pin "M2") (pinfunction "M2_M2") (pintype "bidirectional"))
    )
    (net (code "59") (name "Net-(M3A-S)") (class "Default")
      (node (ref "M3") (pin "1") (pinfunction "S_1") (pintype "passive"))
      (node (ref "MOT3") (pin "M1") (pinfunction "M1_M1") (pintype "bidirectional"))
    )
    (net (code "60") (name "Net-(M3B-S)") (class "Default")
      (node (ref "M3") (pin "2") (pinfunction "S_2") (pintype "passive"))
      (node (ref "MOT3") (pin "M2") (pinfunction "M2_M2") (pintype "bidirectional"))
    )
    (net (code "61") (name "Net-(PWR-Pad2)") (class "Default")
      (node (ref "PWR") (pin "2") (pinfunction "2_2") (pintype "passive"))
      (node (ref "PWR_REG") (pin "EN") (pinfunction "EN_EN") (pintype "bidirectional"))
    )
    (net (code "62") (name "Net-(Q1-PadG)") (class "Default")
      (node (ref "Q1") (pin "G") (pinfunction "G_G") (pintype "passive"))
      (node (ref "R1") (pin "2") (pinfunction "2_2") (pintype "passive"))
    )
    (net (code "63") (name "Net-(Q2-PadG)") (class "Default")
      (node (ref "Q2") (pin "G") (pinfunction "G_G") (pintype "passive"))
      (node (ref "R2") (pin "2") (pinfunction "2_2") (pintype "passive"))
    )
    (net (code "64") (name "Net-(Q3-PadG)") (class "Default")
      (node (ref "Q3") (pin "G") (pinfunction "G_G") (pintype "passive"))
      (node (ref "R3") (pin "2") (pinfunction "2_2") (pintype "passive"))
    )
    (net (code "65") (name "Net-(Q4-PadG)") (class "Default")
      (node (ref "Q4") (pin "G") (pinfunction "G_G") (pintype "passive"))
      (node (ref "R4") (pin "2") (pinfunction "2_2") (pintype "passive"))
    )
    (net (code "66") (name "Net-(Q5-PadG)") (class "Default")
      (node (ref "Q5") (pin "G") (pinfunction "G_G") (pintype "passive"))
      (node (ref "R5") (pin "2") (pinfunction "2_2") (pintype "passive"))
    )
    (net (code "67") (name "Net-(Q6-PadG)") (class "Default")
      (node (ref "Q6") (pin "G") (pinfunction "G_G") (pintype "passive"))
      (node (ref "R6") (pin "2") (pinfunction "2_2") (pintype "passive"))
    )
    (net (code "68") (name "Net-(Q7-PadG)") (class "Default")
      (node (ref "Q7") (pin "G") (pinfunction "G_G") (pintype "passive"))
      (node (ref "R7") (pin "2") (pinfunction "2_2") (pintype "passive"))
    )
    (net (code "69") (name "Net-(Q8-PadG)") (class "Default")
      (node (ref "Q8") (pin "G") (pinfunction "G_G") (pintype "passive"))
      (node (ref "R8") (pin "2") (pinfunction "2_2") (pintype "passive"))
    )
    (net (code "70") (name "Net-(Q9-PadG)") (class "Default")
      (node (ref "Q9") (pin "G") (pinfunction "G_G") (pintype "passive"))
      (node (ref "R9") (pin "2") (pinfunction "2_2") (pintype "passive"))
    )
    (net (code "71") (name "unconnected-(MOT1-PadVM)") (class "Default")
      (node (ref "MOT1") (pin "VM") (pinfunction "VM_VM") (pintype "bidirectional"))
    )
    (net (code "72") (name "unconnected-(MOT2-PadVM)") (class "Default")
      (node (ref "MOT2") (pin "VM") (pinfunction "VM_VM") (pintype "bidirectional"))
    )
    (net (code "73") (name "unconnected-(MOT3-PadVM)") (class "Default")
      (node (ref "MOT3") (pin "VM") (pinfunction "VM_VM") (pintype "bidirectional"))
    )
    (net (code "74") (name "unconnected-(U$2-0{slash}RX1{slash}T-Pad0)") (class "Default")
      (node (ref "U$2") (pin "0") (pinfunction "0/RX1/T_0") (pintype "bidirectional"))
    )
    (net (code "75") (name "unconnected-(U$2-1{slash}TX1{slash}T-Pad1)") (class "Default")
      (node (ref "U$2") (pin "1") (pinfunction "1/TX1/T_1") (pintype "bidirectional"))
    )
    (net (code "76") (name "unconnected-(U$2-A14{slash}DAC-PadRESET{slash}DAC)") (class "Default")
      (node (ref "U$2") (pin "RESET/DAC") (pinfunction "A14/DAC_RESET/DAC") (pintype "bidirectional"))
    )
    (net (code "77") (name "unconnected-(U$2-Pad24)") (class "Default")
      (node (ref "U$2") (pin "24") (pinfunction "24_24") (pintype "bidirectional"))
    )
    (net (code "78") (name "unconnected-(U$2-PadPGM)") (class "Default")
      (node (ref "U$2") (pin "PGM") (pinfunction "PGM_PGM") (pintype "bidirectional"))
    )
  )
)
